# THYRISTOR_POWER_REGULATOR_V2.net
KiCad netlist of a schematic drawn in Altium Designer
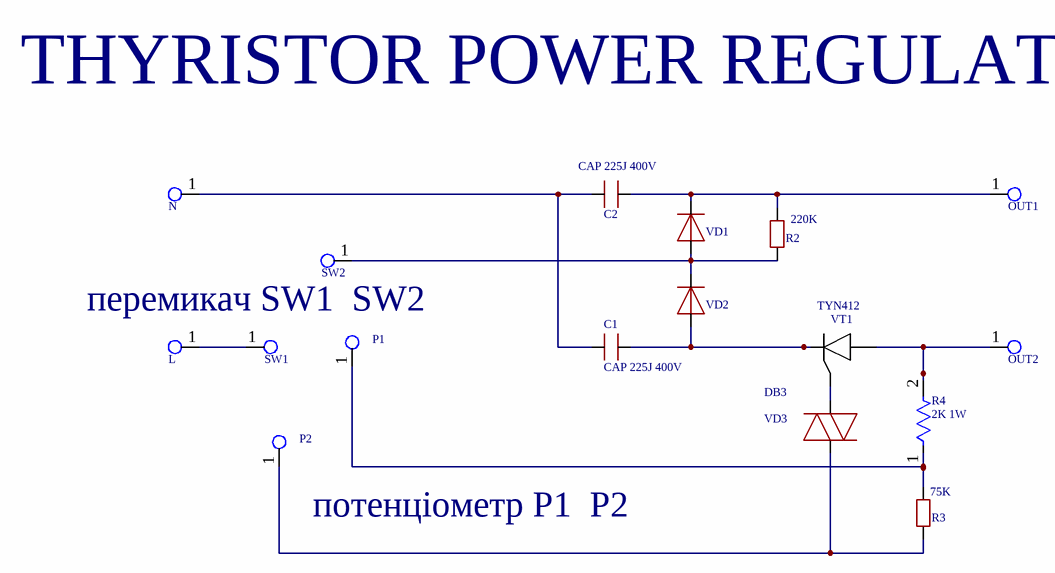
[diagram p0: THYRISTOR POWER REGULATOR_V2..SchDoc]

(export (version "E")
  (design (tool "Eeschema 10.0.6"))
  (components
    (comp (ref "C1")
      (value "CAP 225J 400V")
      (footprint "CAP 225J 400V")
      (libsource (lib "CAP 225J 400V") (part "CAP 225J 400V"))
    )
    (comp (ref "C2")
      (value "CAP 225J 400V")
      (footprint "CAP 225J 400V")
      (libsource (lib "CAP 225J 400V") (part "CAP 225J 400V"))
    )
    (comp (ref "L")
      (value "Test_Point_PCB")
      (footprint "Test_Point")
      (description "Test_Point")
      (libsource (lib "TEST_POINT") (part "TP_PCB?"))
    )
    (comp (ref "N")
      (value "Test_Point_PCB")
      (footprint "Test_Point")
      (description "Test_Point")
      (libsource (lib "") (part "TP_PCB?_1"))
    )
    (comp (ref "OUT1")
      (value "Test_Point_PCB")
      (footprint "Test_Point")
      (description "Test_Point")
      (libsource (lib "TEST_POINT") (part "TP_PCB?"))
    )
    (comp (ref "OUT2")
      (value "Test_Point_PCB")
      (footprint "Test_Point")
      (description "Test_Point")
      (libsource (lib "TEST_POINT") (part "TP_PCB?"))
    )
    (comp (ref "P1")
      (value "Test_Point_PCB")
      (footprint "Test_Point")
      (description "Test_Point")
      (libsource (lib "TEST_POINT") (part "TP_PCB?"))
    )
    (comp (ref "P2")
      (value "Test_Point_PCB")
      (footprint "Test_Point")
      (description "Test_Point")
      (libsource (lib "TEST_POINT") (part "TP_PCB?"))
    )
    (comp (ref "R2") (value "220K") (footprint "RES025W") (libsource (lib "RES") (part "RES")))
    (comp (ref "R3") (value "75K") (footprint "RES025W") (libsource (lib "RES") (part "RES")))
    (comp (ref "R4")
      (value "2K 1W")
      (footprint "RES-2W")
      (description "10K")
      (libsource (lib "PASSIVE_COMPONENTS") (part "RES-CONST"))
    )
    (comp (ref "SW1")
      (value "Test_Point_PCB")
      (footprint "Test_Point")
      (description "Test_Point")
      (libsource (lib "TEST_POINT") (part "TP_PCB?"))
    )
    (comp (ref "SW2")
      (value "Test_Point_PCB")
      (footprint "Test_Point")
      (description "Test_Point")
      (libsource (lib "TEST_POINT") (part "TP_PCB?"))
    )
    (comp (ref "VD1") (value "DIODE") (footprint "FR207") (libsource (lib "FR207") (part "DIODE")))
    (comp (ref "VD2") (value "DIODE") (footprint "FR207") (libsource (lib "FR207") (part "DIODE")))
    (comp (ref "VD3") (value "DB3") (footprint "DB3") (libsource (lib "DB3") (part "DIODE")))
    (comp (ref "VT1") (value "TYN412") (footprint "TO-220-3") (libsource (lib "TYN412") (part "TYN412")))
  )
  (nets
    (net (code "1") (name "Net-(C1-A)") (class "Default")
      (node (ref "C1") (pin "2") (pinfunction "A_2") (pintype "passive"))
      (node (ref "C2") (pin "2") (pinfunction "A_2") (pintype "passive"))
      (node (ref "N") (pin "1") (pinfunction "G9_1") (pintype "passive"))
    )
    (net (code "2") (name "Net-(C1-C)") (class "Default")
      (node (ref "C1") (pin "1") (pinfunction "C_1") (pintype "passive"))
      (node (ref "VD2") (pin "2") (pinfunction "A_2") (pintype "passive"))
      (node (ref "VT1") (pin "1") (pintype "passive"))
    )
    (net (code "3") (name "Net-(C2-C)") (class "Default")
      (node (ref "C2") (pin "1") (pinfunction "C_1") (pintype "passive"))
      (node (ref "OUT1") (pin "1") (pinfunction "G9_1") (pintype "passive"))
      (node (ref "R2") (pin "2") (pintype "passive"))
      (node (ref "VD1") (pin "1") (pinfunction "C_1") (pintype "passive"))
    )
    (net (code "4") (name "Net-(L-G9)") (class "Default")
      (node (ref "L") (pin "1") (pinfunction "G9_1") (pintype "passive"))
      (node (ref "SW1") (pin "1") (pinfunction "G9_1") (pintype "passive"))
    )
    (net (code "5") (name "Net-(OUT2-G9)") (class "Default")
      (node (ref "OUT2") (pin "1") (pinfunction "G9_1") (pintype "passive"))
      (node (ref "R4") (pin "2") (pinfunction "2_2") (pintype "passive"))
      (node (ref "VT1") (pin "2") (pintype "passive"))
    )
    (net (code "6") (name "Net-(P1-G9)") (class "Default")
      (node (ref "P1") (pin "1") (pinfunction "G9_1") (pintype "passive"))
      (node (ref "R3") (pin "2") (pintype "passive"))
      (node (ref "R4") (pin "1") (pinfunction "1_1") (pintype "passive"))
    )
    (net (code "7") (name "Net-(P2-G9)") (class "Default")
      (node (ref "P2") (pin "1") (pinfunction "G9_1") (pintype "passive"))
      (node (ref "R3") (pin "1") (pintype "passive"))
      (node (ref "VD3") (pin "2") (pinfunction "A_2") (pintype "passive"))
    )
    (net (code "8") (name "Net-(SW2-G9)") (class "Default")
      (node (ref "R2") (pin "1") (pintype "passive"))
      (node (ref "SW2") (pin "1") (pinfunction "G9_1") (pintype "passive"))
      (node (ref "VD1") (pin "2") (pinfunction "A_2") (pintype "passive"))
      (node (ref "VD2") (pin "1") (pinfunction "C_1") (pintype "passive"))
    )
    (net (code "9") (name "Net-(VD3-C)") (class "Default")
      (node (ref "VD3") (pin "1") (pinfunction "C_1") (pintype "passive"))
      (node (ref "VT1") (pin "3") (pintype "passive"))
    )
  )
)
